# BuddyBand-BASIC-TOP.net
KiCad netlist of a schematic drawn in EAGLE
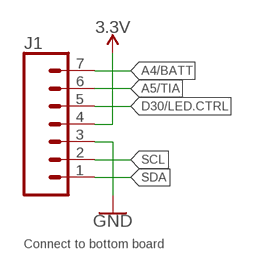
[diagram p0: schematic, sheet 1, part 1 of 2]
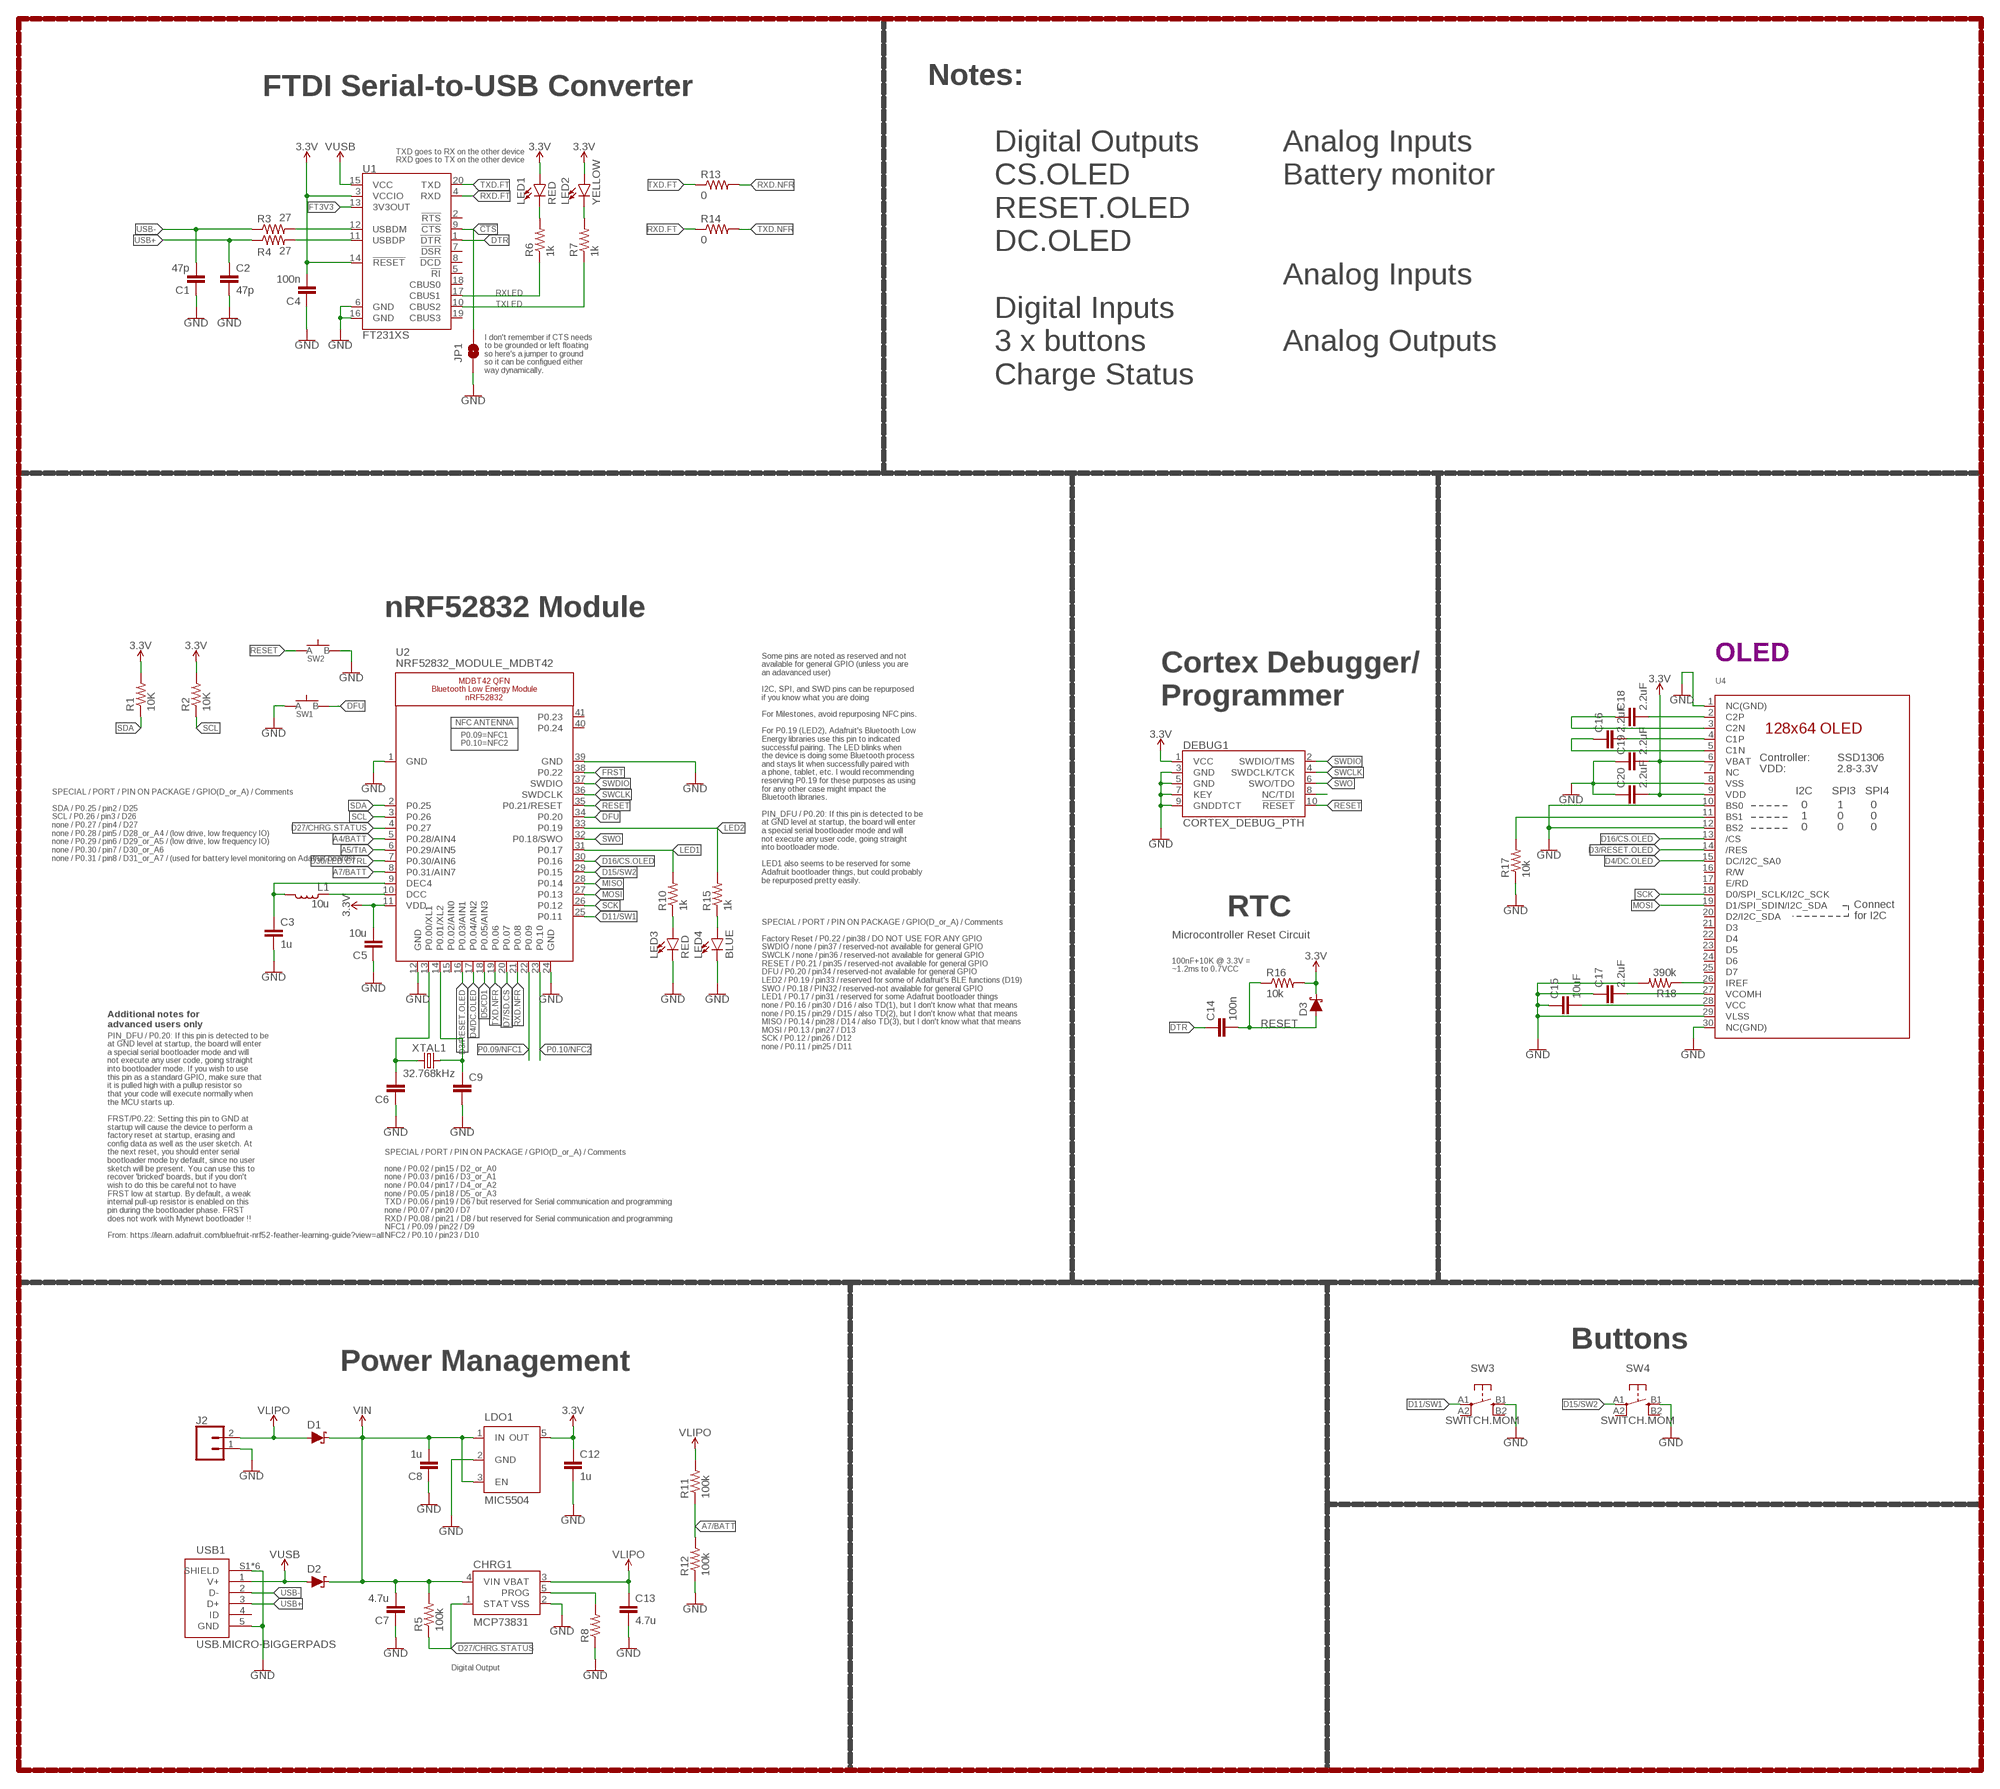
[diagram p1: schematic, sheet 1, part 2 of 2]

(export (version "E")
  (design (tool "Eeschema 10.0.6"))
  (components
    (comp (ref "C1")
      (value "47p")
      (footprint "eagle-import:C0603")
      (libsource (lib "eagle-import") (part "CAPACITOR0603"))
    )
    (comp (ref "C2")
      (value "47p")
      (footprint "eagle-import:C0603")
      (libsource (lib "eagle-import") (part "CAPACITOR0603"))
    )
    (comp (ref "C3")
      (value "1u")
      (footprint "eagle-import:C0603")
      (libsource (lib "eagle-import") (part "CAPACITOR0603"))
    )
    (comp (ref "C4")
      (value "100n")
      (footprint "eagle-import:C0603")
      (libsource (lib "eagle-import") (part "CAPACITOR0603"))
    )
    (comp (ref "C5")
      (value "10u")
      (footprint "eagle-import:C0805")
      (libsource (lib "eagle-import") (part "CAPACITOR0805"))
    )
    (comp (ref "C6")
      (value "CAPACITOR0603")
      (footprint "eagle-import:C0603")
      (libsource (lib "eagle-import") (part "CAPACITOR0603"))
    )
    (comp (ref "C7")
      (value "4.7u")
      (footprint "eagle-import:C0603")
      (libsource (lib "eagle-import") (part "CAPACITOR0603"))
    )
    (comp (ref "C8")
      (value "1u")
      (footprint "eagle-import:C0603")
      (libsource (lib "eagle-import") (part "CAPACITOR0603"))
    )
    (comp (ref "C9")
      (value "CAPACITOR0603")
      (footprint "eagle-import:C0603")
      (libsource (lib "eagle-import") (part "CAPACITOR0603"))
    )
    (comp (ref "C12")
      (value "1u")
      (footprint "eagle-import:C0603")
      (libsource (lib "eagle-import") (part "CAPACITOR0603"))
    )
    (comp (ref "C13")
      (value "4.7u")
      (footprint "eagle-import:C0603")
      (libsource (lib "eagle-import") (part "CAPACITOR0603"))
    )
    (comp (ref "C14")
      (value "100n")
      (footprint "eagle-import:C0603")
      (libsource (lib "eagle-import") (part "CAPACITOR0603"))
    )
    (comp (ref "C15")
      (value "10uF")
      (footprint "eagle-import:C0603")
      (libsource (lib "eagle-import") (part "CAPACITOR0603"))
    )
    (comp (ref "C16")
      (value "2.2uF")
      (footprint "eagle-import:C0402")
      (libsource (lib "eagle-import") (part "CAPACITOR0402"))
    )
    (comp (ref "C17")
      (value "2.2uF")
      (footprint "eagle-import:C0402")
      (libsource (lib "eagle-import") (part "CAPACITOR0402"))
    )
    (comp (ref "C18")
      (value "2.2uF")
      (footprint "eagle-import:C0402")
      (libsource (lib "eagle-import") (part "CAPACITOR0402"))
    )
    (comp (ref "C19")
      (value "2.2uF")
      (footprint "eagle-import:C0402")
      (libsource (lib "eagle-import") (part "CAPACITOR0402"))
    )
    (comp (ref "C20")
      (value "2.2uF")
      (footprint "eagle-import:C0402")
      (libsource (lib "eagle-import") (part "CAPACITOR0402"))
    )
    (comp (ref "CHRG1")
      (value "MCP73831")
      (footprint "eagle-import:SOT23-5")
      (libsource (lib "eagle-import") (part "MCP73831"))
    )
    (comp (ref "D1")
      (value "SCHOTTKY-USC")
      (footprint "eagle-import:USC")
      (libsource (lib "eagle-import") (part "SCHOTTKY-USC"))
    )
    (comp (ref "D2")
      (value "SCHOTTKY-USC")
      (footprint "eagle-import:USC")
      (libsource (lib "eagle-import") (part "SCHOTTKY-USC"))
    )
    (comp (ref "D3")
      (value "SCHOTTKY-USC")
      (footprint "eagle-import:USC")
      (libsource (lib "eagle-import") (part "SCHOTTKY-USC"))
    )
    (comp (ref "DEBUG1")
      (value "CORTEX_DEBUG_PTH")
      (footprint "eagle-import:2X5-PTH-1.27MM")
      (libsource (lib "eagle-import") (part "CORTEX_DEBUG_PTH"))
    )
    (comp (ref "J1")
      (value "CONN_07-1.27MM")
      (footprint "eagle-import:1X07_1.27MM")
      (libsource (lib "eagle-import") (part "CONN_07-1.27MM"))
    )
    (comp (ref "J2")
      (value "CONN_02")
      (footprint "eagle-import:1X02")
      (libsource (lib "eagle-import") (part "CONN_02"))
    )
    (comp (ref "JP1")
      (value "JUMPER-SMT_2_NO_SILK")
      (footprint "eagle-import:SMT-JUMPER_2_NO_SILK")
      (libsource (lib "eagle-import") (part "JUMPER-SMT_2_NO_SILK"))
    )
    (comp (ref "L1")
      (value "10u")
      (footprint "eagle-import:L0603")
      (libsource (lib "eagle-import") (part "INDUCTOR0603"))
    )
    (comp (ref "LDO1")
      (value "MIC5504")
      (footprint "eagle-import:SOT23-5")
      (libsource (lib "eagle-import") (part "MIC5504"))
    )
    (comp (ref "LED1")
      (value "RED")
      (footprint "eagle-import:LED-0603")
      (libsource (lib "eagle-import") (part "LED0603"))
    )
    (comp (ref "LED2")
      (value "YELLOW")
      (footprint "eagle-import:LED-0603")
      (libsource (lib "eagle-import") (part "LED0603"))
    )
    (comp (ref "LED3")
      (value "RED")
      (footprint "eagle-import:LED-0603")
      (libsource (lib "eagle-import") (part "LED0603"))
    )
    (comp (ref "LED4")
      (value "BLUE")
      (footprint "eagle-import:LED-0603")
      (libsource (lib "eagle-import") (part "LED0603"))
    )
    (comp (ref "R1")
      (value "10K")
      (footprint "eagle-import:R0603")
      (libsource (lib "eagle-import") (part "RESISTOR0603"))
    )
    (comp (ref "R2")
      (value "10K")
      (footprint "eagle-import:R0603")
      (libsource (lib "eagle-import") (part "RESISTOR0603"))
    )
    (comp (ref "R3")
      (value "27")
      (footprint "eagle-import:R0603")
      (libsource (lib "eagle-import") (part "RESISTOR0603"))
    )
    (comp (ref "R4")
      (value "27")
      (footprint "eagle-import:R0603")
      (libsource (lib "eagle-import") (part "RESISTOR0603"))
    )
    (comp (ref "R5")
      (value "100k")
      (footprint "eagle-import:R0603")
      (libsource (lib "eagle-import") (part "RESISTOR0603"))
    )
    (comp (ref "R6")
      (value "1k")
      (footprint "eagle-import:R0603")
      (libsource (lib "eagle-import") (part "RESISTOR0603"))
    )
    (comp (ref "R7")
      (value "1k")
      (footprint "eagle-import:R0603")
      (libsource (lib "eagle-import") (part "RESISTOR0603"))
    )
    (comp (ref "R8")
      (value "RESISTOR0603")
      (footprint "eagle-import:R0603")
      (libsource (lib "eagle-import") (part "RESISTOR0603"))
    )
    (comp (ref "R10")
      (value "1k")
      (footprint "eagle-import:R0603")
      (libsource (lib "eagle-import") (part "RESISTOR0603"))
    )
    (comp (ref "R11")
      (value "100k")
      (footprint "eagle-import:R0603")
      (libsource (lib "eagle-import") (part "RESISTOR0603"))
    )
    (comp (ref "R12")
      (value "100k")
      (footprint "eagle-import:R0603")
      (libsource (lib "eagle-import") (part "RESISTOR0603"))
    )
    (comp (ref "R13")
      (value "0")
      (footprint "eagle-import:R0603")
      (libsource (lib "eagle-import") (part "RESISTOR0603"))
    )
    (comp (ref "R14")
      (value "0")
      (footprint "eagle-import:R0603")
      (libsource (lib "eagle-import") (part "RESISTOR0603"))
    )
    (comp (ref "R15")
      (value "1k")
      (footprint "eagle-import:R0603")
      (libsource (lib "eagle-import") (part "RESISTOR0603"))
    )
    (comp (ref "R16")
      (value "10k")
      (footprint "eagle-import:R0603")
      (libsource (lib "eagle-import") (part "RESISTOR0603"))
    )
    (comp (ref "R17")
      (value "10k")
      (footprint "eagle-import:R0603")
      (libsource (lib "eagle-import") (part "RESISTOR0603"))
    )
    (comp (ref "R18")
      (value "390k")
      (footprint "eagle-import:R0603")
      (libsource (lib "eagle-import") (part "RESISTOR0603"))
    )
    (comp (ref "SW1")
      (value "SPST-PTS830GG140-COPY.1-3")
      (footprint "eagle-import:BUTTON-GULLWING")
      (libsource (lib "eagle-import") (part "SPST-PTS830GG140-COPY.1-3"))
    )
    (comp (ref "SW2")
      (value "SPST-PTS830GG140-COPY.1-3")
      (footprint "eagle-import:BUTTON-GULLWING")
      (libsource (lib "eagle-import") (part "SPST-PTS830GG140-COPY.1-3"))
    )
    (comp (ref "SW3")
      (value "SWITCH.MOM")
      (footprint "eagle-import:TACTILE_SWITCH_SMD_6.2MM_TALL")
      (libsource (lib "eagle-import") (part "SWITCH.MOM"))
    )
    (comp (ref "SW4")
      (value "SWITCH.MOM")
      (footprint "eagle-import:TACTILE_SWITCH_SMD_6.2MM_TALL")
      (libsource (lib "eagle-import") (part "SWITCH.MOM"))
    )
    (comp (ref "U1")
      (value "FT231XS")
      (footprint "eagle-import:SSOP20_L")
      (libsource (lib "eagle-import") (part "FT231XS"))
    )
    (comp (ref "U2")
      (value "NRF52832_MODULE_MDBT42")
      (footprint "eagle-import:BLE_MODULE_RAYTAC_MDBT42")
      (libsource (lib "eagle-import") (part "NRF52832_MODULE_MDBT42"))
    )
    (comp (ref "U4")
      (value "DISP_OLED_UG-2864HSWEG01-NO-WRAPAROUND")
      (footprint "eagle-import:UG-2864HSWEG01_0.96IN_NO-WRAPAROUND")
      (libsource (lib "eagle-import") (part "DISP_OLED_UG-2864HSWEG01-NO-WRAPAROUND"))
    )
    (comp (ref "USB1")
      (value "USB.MICRO-BIGGERPADS")
      (footprint "eagle-import:USB-MICRO-01.BIGGERPADS")
      (libsource (lib "eagle-import") (part "USB.MICRO-BIGGERPADS"))
    )
    (comp (ref "XTAL1")
      (value "32.768kHz")
      (footprint "eagle-import:2-SMD.NOLEAD.2.0MMTO1.2MM")
      (libsource (lib "eagle-import") (part "CRYSTALECS-.327-12.5-12-C-TR"))
    )
  )
  (nets
    (net (code "1") (name "/RXLED") (class "Default")
      (node (ref "R6") (pin "1") (pinfunction "1_1") (pintype "passive"))
      (node (ref "U1") (pin "17") (pinfunction "CBUS1_17") (pintype "bidirectional"))
    )
    (net (code "2") (name "/TXLED") (class "Default")
      (node (ref "R7") (pin "1") (pinfunction "1_1") (pintype "passive"))
      (node (ref "U1") (pin "10") (pinfunction "CBUS2_10") (pintype "bidirectional"))
    )
    (net (code "3") (name "/~{CTS}") (class "Default")
      (node (ref "JP1") (pin "2") (pinfunction "2_2") (pintype "passive"))
      (node (ref "U1") (pin "9") (pinfunction "~{CTS}_9") (pintype "bidirectional"))
    )
    (net (code "4") (name "3.3V") (class "Default")
      (node (ref "C12") (pin "1") (pinfunction "1_1") (pintype "passive"))
      (node (ref "C19") (pin "2") (pinfunction "2_2") (pintype "passive"))
      (node (ref "C20") (pin "2") (pinfunction "2_2") (pintype "passive"))
      (node (ref "C4") (pin "2") (pinfunction "2_2") (pintype "passive"))
      (node (ref "C5") (pin "2") (pinfunction "2_2") (pintype "passive"))
      (node (ref "D3") (pin "-") (pinfunction "C_-") (pintype "passive"))
      (node (ref "DEBUG1") (pin "1") (pinfunction "VCC_1") (pintype "bidirectional"))
      (node (ref "J1") (pin "4") (pinfunction "4_4") (pintype "passive"))
      (node (ref "LDO1") (pin "5") (pinfunction "OUT_5") (pintype "bidirectional"))
      (node (ref "LED1") (pin "A") (pinfunction "A_A") (pintype "passive"))
      (node (ref "LED2") (pin "A") (pinfunction "A_A") (pintype "passive"))
      (node (ref "R1") (pin "2") (pinfunction "2_2") (pintype "passive"))
      (node (ref "R16") (pin "2") (pinfunction "2_2") (pintype "passive"))
      (node (ref "R2") (pin "2") (pinfunction "2_2") (pintype "passive"))
      (node (ref "U1") (pin "14") (pinfunction "~{RESET}_14") (pintype "bidirectional"))
      (node (ref "U1") (pin "3") (pinfunction "VCCIO_3") (pintype "bidirectional"))
      (node (ref "U2") (pin "11") (pinfunction "VDD_11") (pintype "bidirectional"))
      (node (ref "U4") (pin "6") (pinfunction "VBAT_6") (pintype "input"))
      (node (ref "U4") (pin "9") (pinfunction "VDD_9") (pintype "power_in"))
    )
    (net (code "5") (name "A4{slash}BATT") (class "Default")
      (node (ref "J1") (pin "7") (pinfunction "7_7") (pintype "passive"))
      (node (ref "U2") (pin "5") (pinfunction "P0.28/AIN4_5") (pintype "bidirectional"))
    )
    (net (code "6") (name "A5{slash}TIA") (class "Default")
      (node (ref "J1") (pin "6") (pinfunction "6_6") (pintype "passive"))
      (node (ref "U2") (pin "6") (pinfunction "P0.29/AIN5_6") (pintype "bidirectional"))
    )
    (net (code "7") (name "A7{slash}BATT") (class "Default")
      (node (ref "R11") (pin "1") (pinfunction "1_1") (pintype "passive"))
      (node (ref "R12") (pin "2") (pinfunction "2_2") (pintype "passive"))
      (node (ref "U2") (pin "8") (pinfunction "P0.31/AIN7_8") (pintype "bidirectional"))
    )
    (net (code "8") (name "D3{slash}RESET.OLED") (class "Default")
      (node (ref "U2") (pin "16") (pinfunction "P0.03/AIN1_16") (pintype "bidirectional"))
      (node (ref "U4") (pin "14") (pinfunction "/RES_14") (pintype "input"))
    )
    (net (code "9") (name "D4{slash}DC.OLED") (class "Default")
      (node (ref "U2") (pin "17") (pinfunction "P0.04/AIN2_17") (pintype "bidirectional"))
      (node (ref "U4") (pin "15") (pinfunction "DC/I2C_SA0_15") (pintype "input"))
    )
    (net (code "10") (name "D5{slash}CD1") (class "Default")
      (node (ref "U2") (pin "18") (pinfunction "P0.05/AIN3_18") (pintype "bidirectional"))
    )
    (net (code "11") (name "D7{slash}SD.CS") (class "Default")
      (node (ref "U2") (pin "20") (pinfunction "P0.07_20") (pintype "bidirectional"))
    )
    (net (code "12") (name "D11{slash}SW1") (class "Default")
      (node (ref "SW3") (pin "A1") (pinfunction "1_A1") (pintype "passive"))
      (node (ref "U2") (pin "25") (pinfunction "P0.11_25") (pintype "bidirectional"))
    )
    (net (code "13") (name "D15{slash}SW2") (class "Default")
      (node (ref "SW4") (pin "A1") (pinfunction "1_A1") (pintype "passive"))
      (node (ref "U2") (pin "29") (pinfunction "P0.15_29") (pintype "bidirectional"))
    )
    (net (code "14") (name "D16{slash}CS.OLED") (class "Default")
      (node (ref "U2") (pin "30") (pinfunction "P0.16_30") (pintype "bidirectional"))
      (node (ref "U4") (pin "13") (pinfunction "/CS_13") (pintype "input"))
    )
    (net (code "15") (name "D27{slash}CHRG.STATUS") (class "Default")
      (node (ref "CHRG1") (pin "1") (pinfunction "STAT_1") (pintype "output"))
      (node (ref "R5") (pin "1") (pinfunction "1_1") (pintype "passive"))
      (node (ref "U2") (pin "4") (pinfunction "P0.27_4") (pintype "bidirectional"))
    )
    (net (code "16") (name "D30{slash}LED.CTRL") (class "Default")
      (node (ref "J1") (pin "5") (pinfunction "5_5") (pintype "passive"))
      (node (ref "U2") (pin "7") (pinfunction "P0.30/AIN6_7") (pintype "bidirectional"))
    )
    (net (code "17") (name "DFU") (class "Default")
      (node (ref "SW1") (pin "3") (pinfunction "B_3") (pintype "bidirectional"))
      (node (ref "U2") (pin "34") (pinfunction "P0.20_34") (pintype "bidirectional"))
    )
    (net (code "18") (name "DTR") (class "Default")
      (node (ref "C14") (pin "1") (pinfunction "1_1") (pintype "passive"))
      (node (ref "U1") (pin "1") (pinfunction "~{DTR}_1") (pintype "bidirectional"))
    )
    (net (code "19") (name "FRST") (class "Default")
      (node (ref "U2") (pin "38") (pinfunction "P0.22_38") (pintype "bidirectional"))
    )
    (net (code "20") (name "FT3V3") (class "Default")
      (node (ref "U1") (pin "13") (pinfunction "3V3OUT_13") (pintype "bidirectional"))
    )
    (net (code "21") (name "GND") (class "Default")
      (node (ref "C1") (pin "1") (pinfunction "1_1") (pintype "passive"))
      (node (ref "C12") (pin "2") (pinfunction "2_2") (pintype "passive"))
      (node (ref "C13") (pin "2") (pinfunction "2_2") (pintype "passive"))
      (node (ref "C15") (pin "1") (pinfunction "1_1") (pintype "passive"))
      (node (ref "C17") (pin "1") (pinfunction "1_1") (pintype "passive"))
      (node (ref "C19") (pin "1") (pinfunction "1_1") (pintype "passive"))
      (node (ref "C2") (pin "2") (pinfunction "2_2") (pintype "passive"))
      (node (ref "C20") (pin "1") (pinfunction "1_1") (pintype "passive"))
      (node (ref "C3") (pin "2") (pinfunction "2_2") (pintype "passive"))
      (node (ref "C4") (pin "1") (pinfunction "1_1") (pintype "passive"))
      (node (ref "C5") (pin "1") (pinfunction "1_1") (pintype "passive"))
      (node (ref "C6") (pin "1") (pinfunction "1_1") (pintype "passive"))
      (node (ref "C7") (pin "1") (pinfunction "1_1") (pintype "passive"))
      (node (ref "C8") (pin "1") (pinfunction "1_1") (pintype "passive"))
      (node (ref "C9") (pin "2") (pinfunction "2_2") (pintype "passive"))
      (node (ref "CHRG1") (pin "2") (pinfunction "VSS_2") (pintype "power_in"))
      (node (ref "DEBUG1") (pin "3") (pinfunction "GND_3") (pintype "bidirectional"))
      (node (ref "DEBUG1") (pin "5") (pinfunction "GND_5") (pintype "bidirectional"))
      (node (ref "DEBUG1") (pin "7") (pinfunction "KEY_7") (pintype "bidirectional"))
      (node (ref "DEBUG1") (pin "9") (pinfunction "GNDDTCT_9") (pintype "bidirectional"))
      (node (ref "J1") (pin "3") (pinfunction "3_3") (pintype "passive"))
      (node (ref "J2") (pin "1") (pinfunction "1_1") (pintype "passive"))
      (node (ref "JP1") (pin "1") (pinfunction "1_1") (pintype "passive"))
      (node (ref "LDO1") (pin "2") (pinfunction "GND_2") (pintype "bidirectional"))
      (node (ref "LED3") (pin "C") (pinfunction "C_C") (pintype "passive"))
      (node (ref "LED4") (pin "C") (pinfunction "C_C") (pintype "passive"))
      (node (ref "R12") (pin "1") (pinfunction "1_1") (pintype "passive"))
      (node (ref "R17") (pin "1") (pinfunction "1_1") (pintype "passive"))
      (node (ref "R18") (pin "2") (pinfunction "2_2") (pintype "passive"))
      (node (ref "R8") (pin "1") (pinfunction "1_1") (pintype "passive"))
      (node (ref "SW1") (pin "1") (pinfunction "A_1") (pintype "bidirectional"))
      (node (ref "SW2") (pin "3") (pinfunction "B_3") (pintype "bidirectional"))
      (node (ref "SW3") (pin "B1") (pinfunction "3_B1") (pintype "passive"))
      (node (ref "SW4") (pin "B1") (pinfunction "3_B1") (pintype "passive"))
      (node (ref "U1") (pin "16") (pinfunction "GND_16") (pintype "bidirectional"))
      (node (ref "U1") (pin "6") (pinfunction "GND_6") (pintype "bidirectional"))
      (node (ref "U2") (pin "1") (pinfunction "GND_1") (pintype "bidirectional"))
      (node (ref "U2") (pin "12") (pinfunction "GND_12") (pintype "bidirectional"))
      (node (ref "U2") (pin "24") (pinfunction "GND_24") (pintype "bidirectional"))
      (node (ref "U2") (pin "39") (pinfunction "GND_39") (pintype "bidirectional"))
      (node (ref "U4") (pin "1") (pinfunction "NC(GND)_1") (pintype "input"))
      (node (ref "U4") (pin "10") (pinfunction "BS0_10") (pintype "input"))
      (node (ref "U4") (pin "12") (pinfunction "BS2_12") (pintype "input"))
      (node (ref "U4") (pin "29") (pinfunction "VLSS_29") (pintype "power_in"))
      (node (ref "U4") (pin "30") (pinfunction "NC(GND)_30") (pintype "input"))
      (node (ref "U4") (pin "8") (pinfunction "VSS_8") (pintype "power_in"))
      (node (ref "USB1") (pin "5") (pinfunction "GND_5") (pintype "bidirectional"))
      (node (ref "USB1") (pin "S1") (pinfunction "SHIELD_S1") (pintype "bidirectional"))
      (node (ref "USB1") (pin "S2") (pinfunction "SHIELD_S2") (pintype "bidirectional"))
      (node (ref "USB1") (pin "S3") (pinfunction "SHIELD_S3") (pintype "bidirectional"))
      (node (ref "USB1") (pin "S4") (pinfunction "SHIELD_S4") (pintype "bidirectional"))
      (node (ref "USB1") (pin "S5") (pinfunction "SHIELD_S5") (pintype "bidirectional"))
      (node (ref "USB1") (pin "S6") (pinfunction "SHIELD_S6") (pintype "bidirectional"))
    )
    (net (code "22") (name "LED1") (class "Default")
      (node (ref "R10") (pin "2") (pinfunction "2_2") (pintype "passive"))
      (node (ref "U2") (pin "31") (pinfunction "P0.17_31") (pintype "bidirectional"))
    )
    (net (code "23") (name "LED2") (class "Default")
      (node (ref "R15") (pin "2") (pinfunction "2_2") (pintype "passive"))
      (node (ref "U2") (pin "33") (pinfunction "P0.19_33") (pintype "bidirectional"))
    )
    (net (code "24") (name "MISO") (class "Default")
      (node (ref "U2") (pin "28") (pinfunction "P0.14_28") (pintype "bidirectional"))
    )
    (net (code "25") (name "MOSI") (class "Default")
      (node (ref "U2") (pin "27") (pinfunction "P0.13_27") (pintype "bidirectional"))
      (node (ref "U4") (pin "19") (pinfunction "D1/SPI_SDIN/I2C_SDA_19") (pintype "bidirectional"))
    )
    (net (code "26") (name "Net-(CHRG1-PROG)") (class "Default")
      (node (ref "CHRG1") (pin "5") (pinfunction "PROG_5") (pintype "input"))
      (node (ref "R8") (pin "2") (pinfunction "2_2") (pintype "passive"))
    )
    (net (code "27") (name "Net-(LED1-PadC)") (class "Default")
      (node (ref "LED1") (pin "C") (pinfunction "C_C") (pintype "passive"))
      (node (ref "R6") (pin "2") (pinfunction "2_2") (pintype "passive"))
    )
    (net (code "28") (name "Net-(LED2-PadC)") (class "Default")
      (node (ref "LED2") (pin "C") (pinfunction "C_C") (pintype "passive"))
      (node (ref "R7") (pin "2") (pinfunction "2_2") (pintype "passive"))
    )
    (net (code "29") (name "Net-(LED3-PadA)") (class "Default")
      (node (ref "LED3") (pin "A") (pinfunction "A_A") (pintype "passive"))
      (node (ref "R10") (pin "1") (pinfunction "1_1") (pintype "passive"))
    )
    (net (code "30") (name "Net-(LED4-PadA)") (class "Default")
      (node (ref "LED4") (pin "A") (pinfunction "A_A") (pintype "passive"))
      (node (ref "R15") (pin "1") (pinfunction "1_1") (pintype "passive"))
    )
    (net (code "31") (name "Net-(U1-USBDM)") (class "Default")
      (node (ref "R3") (pin "2") (pinfunction "2_2") (pintype "passive"))
      (node (ref "U1") (pin "12") (pinfunction "USBDM_12") (pintype "bidirectional"))
    )
    (net (code "32") (name "Net-(U1-USBDP)") (class "Default")
      (node (ref "R4") (pin "2") (pinfunction "2_2") (pintype "passive"))
      (node (ref "U1") (pin "11") (pinfunction "USBDP_11") (pintype "bidirectional"))
    )
    (net (code "33") (name "Net-(U2-DCC)") (class "Default")
      (node (ref "L1") (pin "1") (pinfunction "1_1") (pintype "passive"))
      (node (ref "U2") (pin "10") (pinfunction "DCC_10") (pintype "bidirectional"))
    )
    (net (code "34") (name "Net-(U2-DEC4)") (class "Default")
      (node (ref "C3") (pin "1") (pinfunction "1_1") (pintype "passive"))
      (node (ref "L1") (pin "2") (pinfunction "2_2") (pintype "passive"))
      (node (ref "U2") (pin "9") (pinfunction "DEC4_9") (pintype "bidirectional"))
    )
    (net (code "35") (name "Net-(U2-P0.00{slash}XL1)") (class "Default")
      (node (ref "C6") (pin "2") (pinfunction "2_2") (pintype "passive"))
      (node (ref "U2") (pin "13") (pinfunction "P0.00/XL1_13") (pintype "bidirectional"))
      (node (ref "XTAL1") (pin "P$1") (pinfunction "1_P$1") (pintype "passive"))
    )
    (net (code "36") (name "Net-(U2-P0.01{slash}XL2)") (class "Default")
      (node (ref "C9") (pin "1") (pinfunction "1_1") (pintype "passive"))
      (node (ref "U2") (pin "14") (pinfunction "P0.01/XL2_14") (pintype "bidirectional"))
      (node (ref "XTAL1") (pin "P$2") (pinfunction "2_P$2") (pintype "passive"))
    )
    (net (code "37") (name "Net-(U4-BS1)") (class "Default")
      (node (ref "R17") (pin "2") (pinfunction "2_2") (pintype "passive"))
      (node (ref "U4") (pin "11") (pinfunction "BS1_11") (pintype "input"))
    )
    (net (code "38") (name "Net-(U4-C1N)") (class "Default")
      (node (ref "C16") (pin "1") (pinfunction "1_1") (pintype "passive"))
      (node (ref "U4") (pin "5") (pinfunction "C1N_5") (pintype "input"))
    )
    (net (code "39") (name "Net-(U4-C1P)") (class "Default")
      (node (ref "C16") (pin "2") (pinfunction "2_2") (pintype "passive"))
      (node (ref "U4") (pin "4") (pinfunction "C1P_4") (pintype "input"))
    )
    (net (code "40") (name "Net-(U4-C2N)") (class "Default")
      (node (ref "C18") (pin "1") (pinfunction "1_1") (pintype "passive"))
      (node (ref "U4") (pin "3") (pinfunction "C2N_3") (pintype "input"))
    )
    (net (code "41") (name "Net-(U4-C2P)") (class "Default")
      (node (ref "C18") (pin "2") (pinfunction "2_2") (pintype "passive"))
      (node (ref "U4") (pin "2") (pinfunction "C2P_2") (pintype "input"))
    )
    (net (code "42") (name "Net-(U4-IREF)") (class "Default")
      (node (ref "R18") (pin "1") (pinfunction "1_1") (pintype "passive"))
      (node (ref "U4") (pin "26") (pinfunction "IREF_26") (pintype "input"))
    )
    (net (code "43") (name "Net-(U4-VCC)") (class "Default")
      (node (ref "C15") (pin "2") (pinfunction "2_2") (pintype "passive"))
      (node (ref "U4") (pin "28") (pinfunction "VCC_28") (pintype "power_in"))
    )
    (net (code "44") (name "Net-(U4-VCOMH)") (class "Default")
      (node (ref "C17") (pin "2") (pinfunction "2_2") (pintype "passive"))
      (node (ref "U4") (pin "27") (pinfunction "VCOMH_27") (pintype "output"))
    )
    (net (code "45") (name "P0.09{slash}NFC1") (class "Default")
      (node (ref "U2") (pin "22") (pinfunction "P0.09_22") (pintype "bidirectional"))
    )
    (net (code "46") (name "P0.10{slash}NFC2") (class "Default")
      (node (ref "U2") (pin "23") (pinfunction "P0.10_23") (pintype "bidirectional"))
    )
    (net (code "47") (name "RESET") (class "Default")
      (node (ref "C14") (pin "2") (pinfunction "2_2") (pintype "passive"))
      (node (ref "D3") (pin "+") (pinfunction "A_+") (pintype "passive"))
      (node (ref "DEBUG1") (pin "10") (pinfunction "~{RESET}_10") (pintype "bidirectional"))
      (node (ref "R16") (pin "1") (pinfunction "1_1") (pintype "passive"))
      (node (ref "SW2") (pin "1") (pinfunction "A_1") (pintype "bidirectional"))
      (node (ref "U2") (pin "35") (pinfunction "P0.21/RESET_35") (pintype "bidirectional"))
    )
    (net (code "48") (name "RXD.FT") (class "Default")
      (node (ref "R14") (pin "1") (pinfunction "1_1") (pintype "passive"))
      (node (ref "U1") (pin "4") (pinfunction "RXD_4") (pintype "bidirectional"))
    )
    (net (code "49") (name "RXD.NFR") (class "Default")
      (node (ref "R13") (pin "2") (pinfunction "2_2") (pintype "passive"))
      (node (ref "U2") (pin "21") (pinfunction "P0.08_21") (pintype "bidirectional"))
    )
    (net (code "50") (name "SCK") (class "Default")
      (node (ref "U2") (pin "26") (pinfunction "P0.12_26") (pintype "bidirectional"))
      (node (ref "U4") (pin "18") (pinfunction "D0/SPI_SCLK/I2C_SCK_18") (pintype "bidirectional"))
    )
    (net (code "51") (name "SCL") (class "Default")
      (node (ref "J1") (pin "2") (pinfunction "2_2") (pintype "passive"))
      (node (ref "R2") (pin "1") (pinfunction "1_1") (pintype "passive"))
      (node (ref "U2") (pin "3") (pinfunction "P0.26_3") (pintype "bidirectional"))
    )
    (net (code "52") (name "SDA") (class "Default")
      (node (ref "J1") (pin "1") (pinfunction "1_1") (pintype "passive"))
      (node (ref "R1") (pin "1") (pinfunction "1_1") (pintype "passive"))
      (node (ref "U2") (pin "2") (pinfunction "P0.25_2") (pintype "bidirectional"))
    )
    (net (code "53") (name "SWCLK") (class "Default")
      (node (ref "DEBUG1") (pin "4") (pinfunction "SWDCLK/TCK_4") (pintype "bidirectional"))
      (node (ref "U2") (pin "36") (pinfunction "SWDCLK_36") (pintype "bidirectional"))
    )
    (net (code "54") (name "SWDIO") (class "Default")
      (node (ref "DEBUG1") (pin "2") (pinfunction "SWDIO/TMS_2") (pintype "bidirectional"))
      (node (ref "U2") (pin "37") (pinfunction "SWDIO_37") (pintype "bidirectional"))
    )
    (net (code "55") (name "SWO") (class "Default")
      (node (ref "DEBUG1") (pin "6") (pinfunction "SWO/TDO_6") (pintype "bidirectional"))
      (node (ref "U2") (pin "32") (pinfunction "P0.18/SWO_32") (pintype "bidirectional"))
    )
    (net (code "56") (name "TXD.FT") (class "Default")
      (node (ref "R13") (pin "1") (pinfunction "1_1") (pintype "passive"))
      (node (ref "U1") (pin "20") (pinfunction "TXD_20") (pintype "bidirectional"))
    )
    (net (code "57") (name "TXD.NFR") (class "Default")
      (node (ref "R14") (pin "2") (pinfunction "2_2") (pintype "passive"))
      (node (ref "U2") (pin "19") (pinfunction "P0.06_19") (pintype "bidirectional"))
    )
    (net (code "58") (name "USB+") (class "Default")
      (node (ref "C2") (pin "1") (pinfunction "1_1") (pintype "passive"))
      (node (ref "R4") (pin "1") (pinfunction "1_1") (pintype "passive"))
      (node (ref "USB1") (pin "3") (pinfunction "D+_3") (pintype "bidirectional"))
    )
    (net (code "59") (name "USB-") (class "Default")
      (node (ref "C1") (pin "2") (pinfunction "2_2") (pintype "passive"))
      (node (ref "R3") (pin "1") (pinfunction "1_1") (pintype "passive"))
      (node (ref "USB1") (pin "2") (pinfunction "D-_2") (pintype "bidirectional"))
    )
    (net (code "60") (name "VIN") (class "Default")
      (node (ref "C7") (pin "2") (pinfunction "2_2") (pintype "passive"))
      (node (ref "C8") (pin "2") (pinfunction "2_2") (pintype "passive"))
      (node (ref "CHRG1") (pin "4") (pinfunction "VIN_4") (pintype "power_in"))
      (node (ref "D1") (pin "-") (pinfunction "C_-") (pintype "passive"))
      (node (ref "D2") (pin "-") (pinfunction "C_-") (pintype "passive"))
      (node (ref "LDO1") (pin "1") (pinfunction "IN_1") (pintype "bidirectional"))
      (node (ref "LDO1") (pin "3") (pinfunction "EN_3") (pintype "bidirectional"))
      (node (ref "R5") (pin "2") (pinfunction "2_2") (pintype "passive"))
    )
    (net (code "61") (name "VLIPO") (class "Default")
      (node (ref "C13") (pin "1") (pinfunction "1_1") (pintype "passive"))
      (node (ref "CHRG1") (pin "3") (pinfunction "VBAT_3") (pintype "power_in"))
      (node (ref "D1") (pin "+") (pinfunction "A_+") (pintype "passive"))
      (node (ref "J2") (pin "2") (pinfunction "2_2") (pintype "passive"))
      (node (ref "R11") (pin "2") (pinfunction "2_2") (pintype "passive"))
    )
    (net (code "62") (name "VUSB") (class "Default")
      (node (ref "D2") (pin "+") (pinfunction "A_+") (pintype "passive"))
      (node (ref "U1") (pin "15") (pinfunction "VCC_15") (pintype "bidirectional"))
      (node (ref "USB1") (pin "1") (pinfunction "V+_1") (pintype "bidirectional"))
    )
    (net (code "63") (name "unconnected-(DEBUG1-NC{slash}TDI-Pad8)") (class "Default")
      (node (ref "DEBUG1") (pin "8") (pinfunction "NC/TDI_8") (pintype "bidirectional"))
    )
    (net (code "64") (name "unconnected-(SW3-2-PadA2)") (class "Default")
      (node (ref "SW3") (pin "A2") (pinfunction "2_A2") (pintype "passive"))
    )
    (net (code "65") (name "unconnected-(SW3-4-PadB2)") (class "Default")
      (node (ref "SW3") (pin "B2") (pinfunction "4_B2") (pintype "passive"))
    )
    (net (code "66") (name "unconnected-(SW4-2-PadA2)") (class "Default")
      (node (ref "SW4") (pin "A2") (pinfunction "2_A2") (pintype "passive"))
    )
    (net (code "67") (name "unconnected-(SW4-4-PadB2)") (class "Default")
      (node (ref "SW4") (pin "B2") (pinfunction "4_B2") (pintype "passive"))
    )
    (net (code "68") (name "unconnected-(U1-CBUS0-Pad18)") (class "Default")
      (node (ref "U1") (pin "18") (pinfunction "CBUS0_18") (pintype "bidirectional"))
    )
    (net (code "69") (name "unconnected-(U1-CBUS3-Pad19)") (class "Default")
      (node (ref "U1") (pin "19") (pinfunction "CBUS3_19") (pintype "bidirectional"))
    )
    (net (code "70") (name "unconnected-(U1-~{DCD}-Pad8)") (class "Default")
      (node (ref "U1") (pin "8") (pinfunction "~{DCD}_8") (pintype "bidirectional"))
    )
    (net (code "71") (name "unconnected-(U1-~{DSR}-Pad7)") (class "Default")
      (node (ref "U1") (pin "7") (pinfunction "~{DSR}_7") (pintype "bidirectional"))
    )
    (net (code "72") (name "unconnected-(U1-~{RI}-Pad5)") (class "Default")
      (node (ref "U1") (pin "5") (pinfunction "~{RI}_5") (pintype "bidirectional"))
    )
    (net (code "73") (name "unconnected-(U1-~{RTS}-Pad2)") (class "Default")
      (node (ref "U1") (pin "2") (pinfunction "~{RTS}_2") (pintype "bidirectional"))
    )
    (net (code "74") (name "unconnected-(U2-P0.02{slash}AIN0-Pad15)") (class "Default")
      (node (ref "U2") (pin "15") (pinfunction "P0.02/AIN0_15") (pintype "bidirectional"))
    )
    (net (code "75") (name "unconnected-(U2-P0.23-Pad41)") (class "Default")
      (node (ref "U2") (pin "41") (pinfunction "P0.23_41") (pintype "bidirectional"))
    )
    (net (code "76") (name "unconnected-(U2-P0.24-Pad40)") (class "Default")
      (node (ref "U2") (pin "40") (pinfunction "P0.24_40") (pintype "bidirectional"))
    )
    (net (code "77") (name "unconnected-(U4-D2{slash}I2C_SDA-Pad20)") (class "Default")
      (node (ref "U4") (pin "20") (pinfunction "D2/I2C_SDA_20") (pintype "bidirectional"))
    )
    (net (code "78") (name "unconnected-(U4-D3-Pad21)") (class "Default")
      (node (ref "U4") (pin "21") (pinfunction "D3_21") (pintype "bidirectional"))
    )
    (net (code "79") (name "unconnected-(U4-D4-Pad22)") (class "Default")
      (node (ref "U4") (pin "22") (pinfunction "D4_22") (pintype "bidirectional"))
    )
    (net (code "80") (name "unconnected-(U4-D5-Pad23)") (class "Default")
      (node (ref "U4") (pin "23") (pinfunction "D5_23") (pintype "bidirectional"))
    )
    (net (code "81") (name "unconnected-(U4-D6-Pad24)") (class "Default")
      (node (ref "U4") (pin "24") (pinfunction "D6_24") (pintype "bidirectional"))
    )
    (net (code "82") (name "unconnected-(U4-D7-Pad25)") (class "Default")
      (node (ref "U4") (pin "25") (pinfunction "D7_25") (pintype "bidirectional"))
    )
    (net (code "83") (name "unconnected-(U4-E{slash}RD-Pad17)") (class "Default")
      (node (ref "U4") (pin "17") (pinfunction "E/RD_17") (pintype "input"))
    )
    (net (code "84") (name "unconnected-(U4-NC-Pad7)") (class "Default")
      (node (ref "U4") (pin "7") (pinfunction "NC_7") (pintype "no_connect"))
    )
    (net (code "85") (name "unconnected-(U4-R{slash}W-Pad16)") (class "Default")
      (node (ref "U4") (pin "16") (pinfunction "R/W_16") (pintype "input"))
    )
    (net (code "86") (name "unconnected-(USB1-ID-Pad4)") (class "Default")
      (node (ref "USB1") (pin "4") (pinfunction "ID_4") (pintype "bidirectional"))
    )
  )
)
